# nintendac_mini.net
KiCad netlist of a schematic drawn in EAGLE
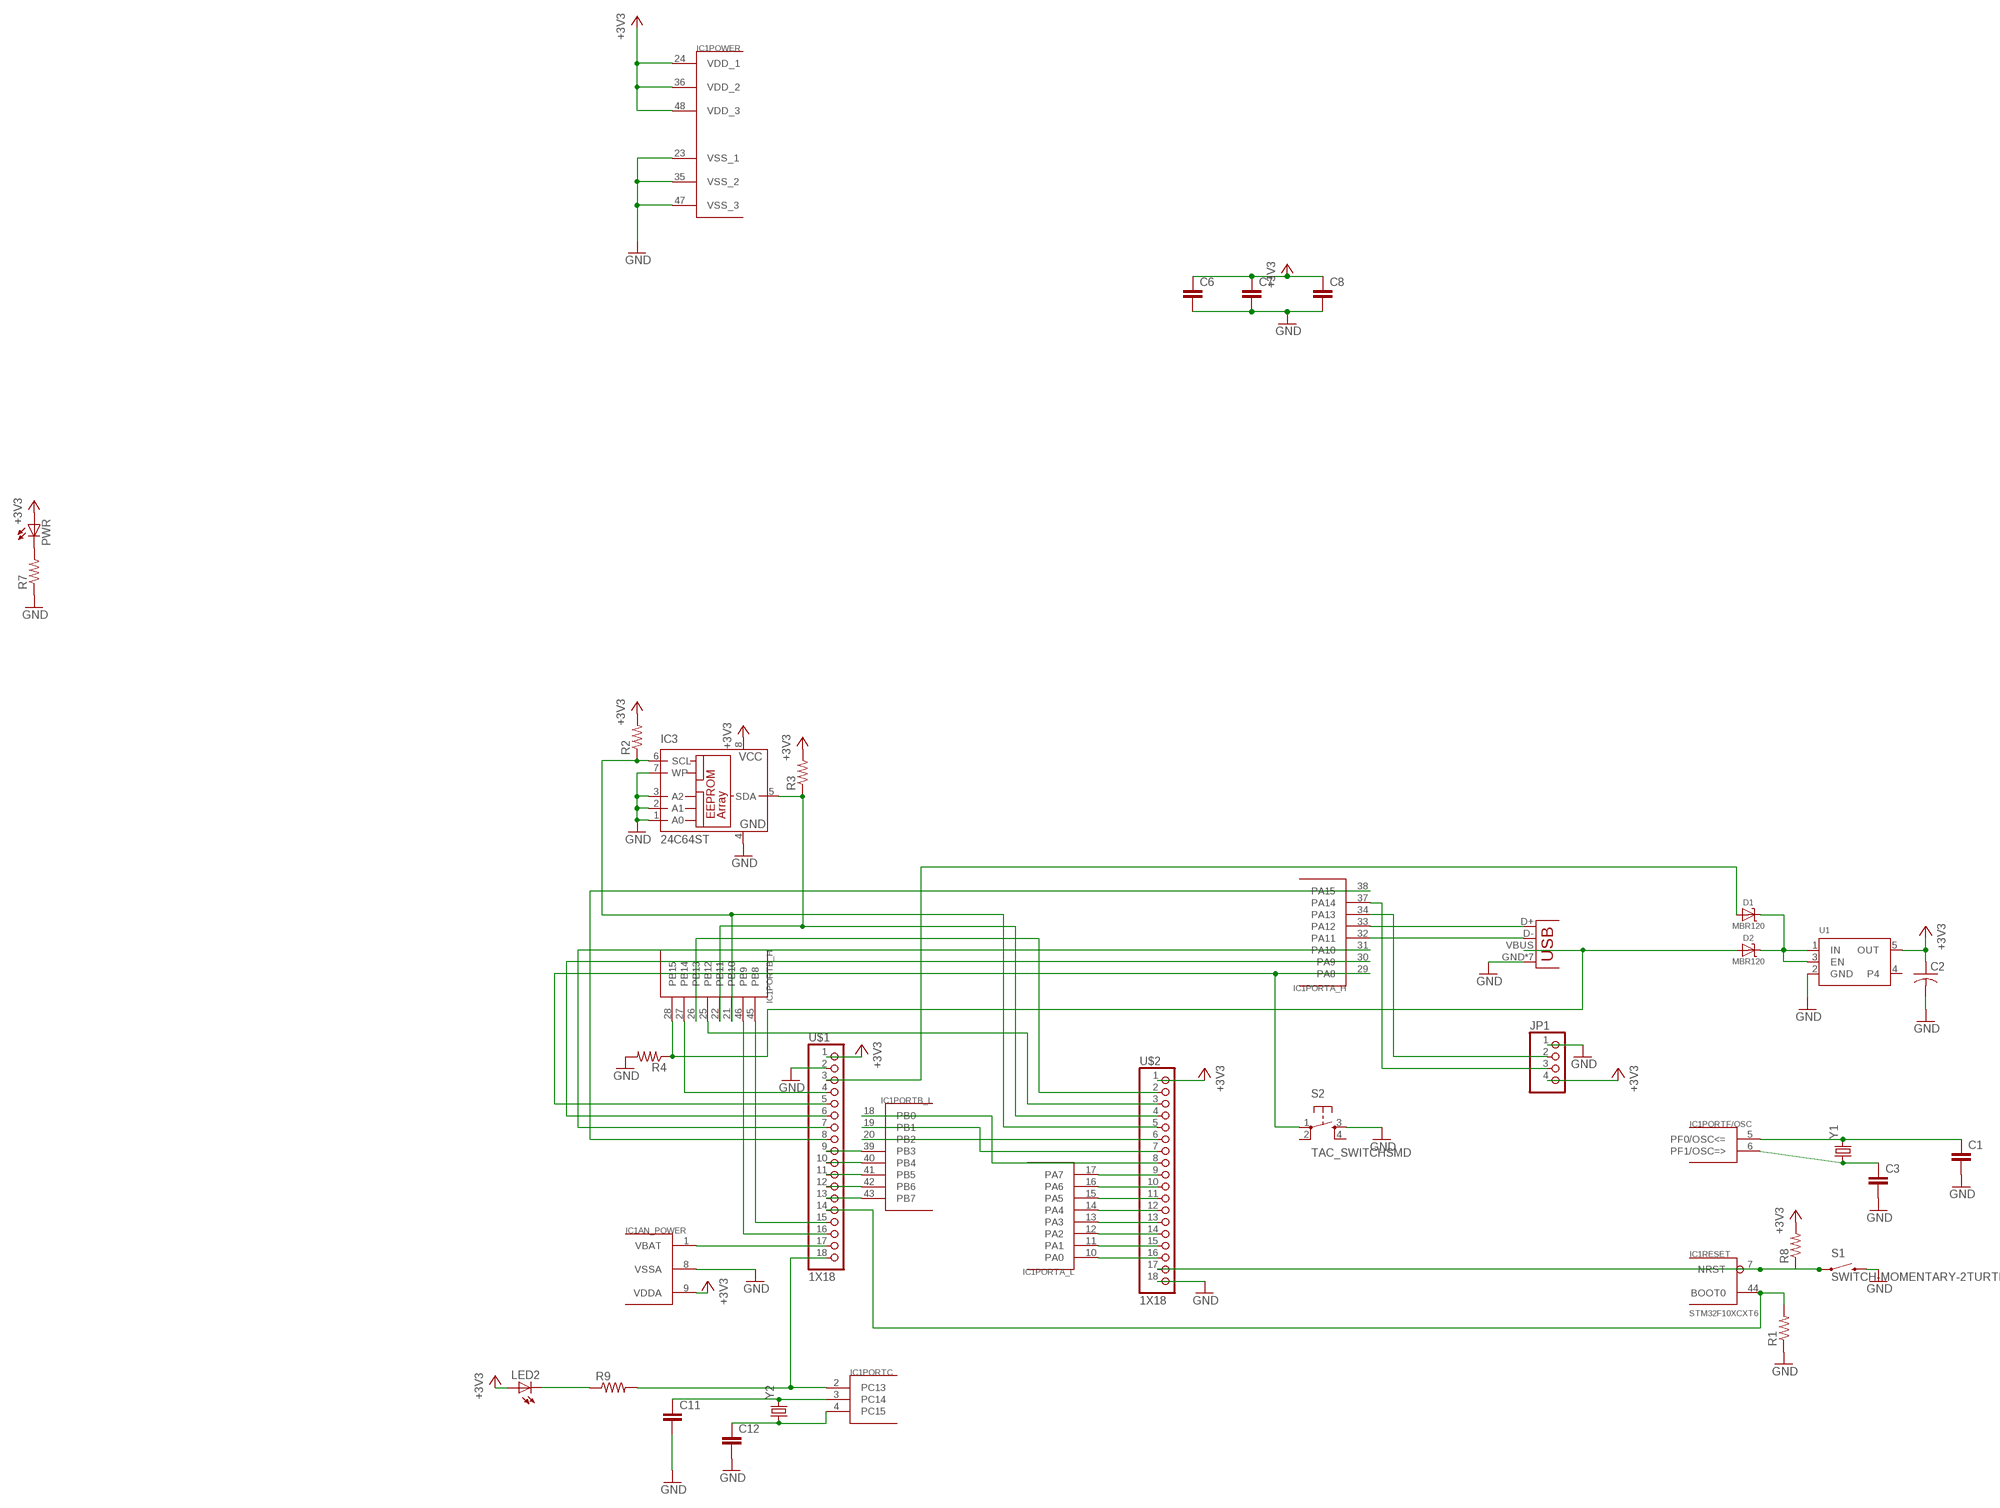
[diagram p0: schematic, sheet 1]

(export (version "E")
  (design (tool "Eeschema 10.0.6"))
  (components
    (comp (ref "C1")
      (value "CAP0805")
      (footprint "eagle-import:0805")
      (libsource (lib "eagle-import") (part "CAP0805"))
    )
    (comp (ref "C2")
      (value "C-USC1210")
      (footprint "eagle-import:C1210")
      (libsource (lib "eagle-import") (part "C-USC1210"))
    )
    (comp (ref "C3")
      (value "CAP0805")
      (footprint "eagle-import:0805")
      (libsource (lib "eagle-import") (part "CAP0805"))
    )
    (comp (ref "C6")
      (value "CAP0805")
      (footprint "eagle-import:0805")
      (libsource (lib "eagle-import") (part "CAP0805"))
    )
    (comp (ref "C7")
      (value "CAP0805")
      (footprint "eagle-import:0805")
      (libsource (lib "eagle-import") (part "CAP0805"))
    )
    (comp (ref "C8")
      (value "CAP0805")
      (footprint "eagle-import:0805")
      (libsource (lib "eagle-import") (part "CAP0805"))
    )
    (comp (ref "C11")
      (value "CAP0805")
      (footprint "eagle-import:0805")
      (libsource (lib "eagle-import") (part "CAP0805"))
    )
    (comp (ref "C12")
      (value "CAP0805")
      (footprint "eagle-import:0805")
      (libsource (lib "eagle-import") (part "CAP0805"))
    )
    (comp (ref "D1")
      (value "MBR120")
      (footprint "eagle-import:SOD-123")
      (libsource (lib "eagle-import") (part "DIODE-SCHOTTKYSOD-123"))
    )
    (comp (ref "D2")
      (value "MBR120")
      (footprint "eagle-import:SOD-123")
      (libsource (lib "eagle-import") (part "DIODE-SCHOTTKYSOD-123"))
    )
    (comp (ref "IC1")
      (value "STM32F10XCXT6")
      (footprint "eagle-import:TQFP48")
      (libsource (lib "eagle-import") (part "STM32F10XCXT6"))
    )
    (comp (ref "IC3")
      (value "24C64ST")
      (footprint "eagle-import:TSSOP8")
      (fields (field (name "MPN") "CAT24C64YI-GT3"))
      (libsource (lib "eagle-import") (part "24STC64"))
    )
    (comp (ref "JP1")
      (value "PINHD-1X4")
      (footprint "eagle-import:1X04")
      (libsource (lib "eagle-import") (part "PINHD-1X4"))
    )
    (comp (ref "LED2")
      (value "LEDCHIP-LED0805")
      (footprint "eagle-import:CHIP-LED0805")
      (libsource (lib "eagle-import") (part "LEDCHIP-LED0805"))
    )
    (comp (ref "PWR")
      (value "LEDCHIP-LED0805")
      (footprint "eagle-import:CHIP-LED0805")
      (libsource (lib "eagle-import") (part "LEDCHIP-LED0805"))
    )
    (comp (ref "R1")
      (value "RESISTOR0805-RES")
      (footprint "eagle-import:0805")
      (libsource (lib "eagle-import") (part "RESISTOR0805-RES"))
    )
    (comp (ref "R2")
      (value "RESISTOR0805-RES")
      (footprint "eagle-import:0805")
      (libsource (lib "eagle-import") (part "RESISTOR0805-RES"))
    )
    (comp (ref "R3")
      (value "RESISTOR0805-RES")
      (footprint "eagle-import:0805")
      (libsource (lib "eagle-import") (part "RESISTOR0805-RES"))
    )
    (comp (ref "R4")
      (value "RESISTOR0805-RES")
      (footprint "eagle-import:0805")
      (libsource (lib "eagle-import") (part "RESISTOR0805-RES"))
    )
    (comp (ref "R7")
      (value "RESISTOR0805-RES")
      (footprint "eagle-import:0805")
      (libsource (lib "eagle-import") (part "RESISTOR0805-RES"))
    )
    (comp (ref "R8")
      (value "RESISTOR0805-RES")
      (footprint "eagle-import:0805")
      (libsource (lib "eagle-import") (part "RESISTOR0805-RES"))
    )
    (comp (ref "R9")
      (value "RESISTOR0805-RES")
      (footprint "eagle-import:0805")
      (libsource (lib "eagle-import") (part "RESISTOR0805-RES"))
    )
    (comp (ref "S1")
      (value "SWITCH-MOMENTARY-2TURTLE")
      (footprint "eagle-import:KMR2")
      (libsource (lib "eagle-import") (part "SWITCH-MOMENTARY-2TURTLE"))
    )
    (comp (ref "S2")
      (value "TAC_SWITCHSMD")
      (footprint "eagle-import:TACTILE-SWITCH-SMD")
      (libsource (lib "eagle-import") (part "TAC_SWITCHSMD"))
    )
    (comp (ref "U$1")
      (value "1X18")
      (footprint "eagle-import:1X18")
      (libsource (lib "eagle-import") (part "1X18"))
    )
    (comp (ref "U$2")
      (value "1X18")
      (footprint "eagle-import:1X18")
      (libsource (lib "eagle-import") (part "1X18"))
    )
    (comp (ref "U1")
      (value "VREG_SOT23-5")
      (footprint "eagle-import:SOT23-5")
      (libsource (lib "eagle-import") (part "VREG_SOT23-5"))
    )
    (comp (ref "X1")
      (value "USB-MICROB")
      (footprint "eagle-import:USB-MICROB")
      (libsource (lib "eagle-import") (part "USB-MICROB"))
    )
    (comp (ref "Y1")
      (value "CRYSTALHC49US")
      (footprint "eagle-import:HC49US")
      (libsource (lib "eagle-import") (part "CRYSTALHC49US"))
    )
    (comp (ref "Y2")
      (value "CRYSTALTC26H_EZ")
      (footprint "eagle-import:TC26HEZ")
      (libsource (lib "eagle-import") (part "CRYSTALTC26H_EZ"))
    )
  )
  (nets
    (net (code "1") (name "+3V3") (class "Default")
      (node (ref "C2") (pin "1") (pinfunction "1_1") (pintype "passive"))
      (node (ref "C6") (pin "1") (pinfunction "1_1") (pintype "passive"))
      (node (ref "C7") (pin "1") (pinfunction "1_1") (pintype "passive"))
      (node (ref "C8") (pin "1") (pinfunction "1_1") (pintype "passive"))
      (node (ref "IC1") (pin "24") (pinfunction "VDD_1_24") (pintype "power_in"))
      (node (ref "IC1") (pin "36") (pinfunction "VDD_2_36") (pintype "power_in"))
      (node (ref "IC1") (pin "48") (pinfunction "VDD_3_48") (pintype "power_in"))
      (node (ref "IC1") (pin "9") (pinfunction "VDDA_9") (pintype "power_in"))
      (node (ref "IC3") (pin "8") (pinfunction "VCC_8") (pintype "power_in"))
      (node (ref "JP1") (pin "4") (pinfunction "4_4") (pintype "passive"))
      (node (ref "LED2") (pin "A") (pinfunction "A_A") (pintype "passive"))
      (node (ref "PWR") (pin "A") (pinfunction "A_A") (pintype "passive"))
      (node (ref "R2") (pin "2") (pinfunction "2_2") (pintype "passive"))
      (node (ref "R3") (pin "2") (pinfunction "2_2") (pintype "passive"))
      (node (ref "R8") (pin "2") (pinfunction "2_2") (pintype "passive"))
      (node (ref "U$1") (pin "1") (pinfunction "1_1") (pintype "passive"))
      (node (ref "U$2") (pin "1") (pinfunction "1_1") (pintype "passive"))
      (node (ref "U1") (pin "5") (pinfunction "OUT_5") (pintype "power_in"))
    )
    (net (code "2") (name "GND") (class "Default")
      (node (ref "C1") (pin "2") (pinfunction "2_2") (pintype "passive"))
      (node (ref "C11") (pin "2") (pinfunction "2_2") (pintype "passive"))
      (node (ref "C12") (pin "2") (pinfunction "2_2") (pintype "passive"))
      (node (ref "C2") (pin "2") (pinfunction "2_2") (pintype "passive"))
      (node (ref "C3") (pin "2") (pinfunction "2_2") (pintype "passive"))
      (node (ref "C6") (pin "2") (pinfunction "2_2") (pintype "passive"))
      (node (ref "C7") (pin "2") (pinfunction "2_2") (pintype "passive"))
      (node (ref "C8") (pin "2") (pinfunction "2_2") (pintype "passive"))
      (node (ref "IC1") (pin "23") (pinfunction "VSS_1_23") (pintype "power_in"))
      (node (ref "IC1") (pin "35") (pinfunction "VSS_2_35") (pintype "power_in"))
      (node (ref "IC1") (pin "47") (pinfunction "VSS_3_47") (pintype "power_in"))
      (node (ref "IC1") (pin "8") (pinfunction "VSSA_8") (pintype "power_in"))
      (node (ref "IC3") (pin "1") (pinfunction "A0_1") (pintype "input"))
      (node (ref "IC3") (pin "2") (pinfunction "A1_2") (pintype "input"))
      (node (ref "IC3") (pin "3") (pinfunction "A2_3") (pintype "input"))
      (node (ref "IC3") (pin "4") (pinfunction "GND_4") (pintype "power_in"))
      (node (ref "IC3") (pin "7") (pinfunction "WP_7") (pintype "input"))
      (node (ref "JP1") (pin "1") (pinfunction "1_1") (pintype "passive"))
      (node (ref "R1") (pin "1") (pinfunction "1_1") (pintype "passive"))
      (node (ref "R4") (pin "2") (pinfunction "2_2") (pintype "passive"))
      (node (ref "R7") (pin "1") (pinfunction "1_1") (pintype "passive"))
      (node (ref "S1") (pin "3") (pinfunction "2_3") (pintype "passive"))
      (node (ref "S2") (pin "3") (pinfunction "3_3") (pintype "passive"))
      (node (ref "U$1") (pin "2") (pinfunction "2_2") (pintype "passive"))
      (node (ref "U$2") (pin "18") (pinfunction "18_18") (pintype "passive"))
      (node (ref "U1") (pin "2") (pinfunction "GND_2") (pintype "power_in"))
      (node (ref "X1") (pin "GND") (pinfunction "GND_GND") (pintype "bidirectional"))
      (node (ref "X1") (pin "P1") (pinfunction "GND_P1") (pintype "bidirectional"))
      (node (ref "X1") (pin "P2") (pinfunction "GND_P2") (pintype "bidirectional"))
      (node (ref "X1") (pin "P3") (pinfunction "GND_P3") (pintype "bidirectional"))
      (node (ref "X1") (pin "P4") (pinfunction "GND_P4") (pintype "bidirectional"))
      (node (ref "X1") (pin "P5") (pinfunction "GND_P5") (pintype "bidirectional"))
      (node (ref "X1") (pin "P6") (pinfunction "GND_P6") (pintype "bidirectional"))
    )
    (net (code "3") (name "Net-(D1-PadA)") (class "Default")
      (node (ref "D1") (pin "A") (pinfunction "A_A") (pintype "passive"))
      (node (ref "U$1") (pin "3") (pinfunction "3_3") (pintype "passive"))
    )
    (net (code "4") (name "Net-(IC1A-VBAT)") (class "Default")
      (node (ref "IC1") (pin "1") (pinfunction "VBAT_1") (pintype "power_in"))
      (node (ref "U$1") (pin "17") (pinfunction "17_17") (pintype "passive"))
    )
    (net (code "5") (name "Net-(IC1B-PA8)") (class "Default")
      (node (ref "IC1") (pin "29") (pinfunction "PA8_29") (pintype "bidirectional"))
      (node (ref "S2") (pin "1") (pinfunction "1_1") (pintype "passive"))
      (node (ref "U$1") (pin "5") (pinfunction "5_5") (pintype "passive"))
    )
    (net (code "6") (name "Net-(IC1B-PA9)") (class "Default")
      (node (ref "IC1") (pin "30") (pinfunction "PA9_30") (pintype "bidirectional"))
      (node (ref "U$1") (pin "6") (pinfunction "6_6") (pintype "passive"))
    )
    (net (code "7") (name "Net-(IC1B-PA10)") (class "Default")
      (node (ref "IC1") (pin "31") (pinfunction "PA10_31") (pintype "bidirectional"))
      (node (ref "U$1") (pin "7") (pinfunction "7_7") (pintype "passive"))
    )
    (net (code "8") (name "Net-(IC1B-PA11)") (class "Default")
      (node (ref "IC1") (pin "32") (pinfunction "PA11_32") (pintype "bidirectional"))
      (node (ref "X1") (pin "D-") (pinfunction "D-_D-") (pintype "bidirectional"))
    )
    (net (code "9") (name "Net-(IC1B-PA12)") (class "Default")
      (node (ref "IC1") (pin "33") (pinfunction "PA12_33") (pintype "bidirectional"))
      (node (ref "X1") (pin "D+") (pinfunction "D+_D+") (pintype "bidirectional"))
    )
    (net (code "10") (name "Net-(IC1B-PA13)") (class "Default")
      (node (ref "IC1") (pin "34") (pinfunction "PA13_34") (pintype "bidirectional"))
      (node (ref "JP1") (pin "2") (pinfunction "2_2") (pintype "passive"))
    )
    (net (code "11") (name "Net-(IC1B-PA14)") (class "Default")
      (node (ref "IC1") (pin "37") (pinfunction "PA14_37") (pintype "bidirectional"))
      (node (ref "JP1") (pin "3") (pinfunction "3_3") (pintype "passive"))
    )
    (net (code "12") (name "Net-(IC1B-PA15)") (class "Default")
      (node (ref "IC1") (pin "38") (pinfunction "PA15_38") (pintype "bidirectional"))
      (node (ref "U$1") (pin "8") (pinfunction "8_8") (pintype "passive"))
    )
    (net (code "13") (name "Net-(IC1C-PA0)") (class "Default")
      (node (ref "IC1") (pin "10") (pinfunction "PA0_10") (pintype "bidirectional"))
      (node (ref "U$2") (pin "16") (pinfunction "16_16") (pintype "passive"))
    )
    (net (code "14") (name "Net-(IC1C-PA1)") (class "Default")
      (node (ref "IC1") (pin "11") (pinfunction "PA1_11") (pintype "bidirectional"))
      (node (ref "U$2") (pin "15") (pinfunction "15_15") (pintype "passive"))
    )
    (net (code "15") (name "Net-(IC1C-PA2)") (class "Default")
      (node (ref "IC1") (pin "12") (pinfunction "PA2_12") (pintype "bidirectional"))
      (node (ref "U$2") (pin "14") (pinfunction "14_14") (pintype "passive"))
    )
    (net (code "16") (name "Net-(IC1C-PA3)") (class "Default")
      (node (ref "IC1") (pin "13") (pinfunction "PA3_13") (pintype "bidirectional"))
      (node (ref "U$2") (pin "13") (pinfunction "13_13") (pintype "passive"))
    )
    (net (code "17") (name "Net-(IC1C-PA4)") (class "Default")
      (node (ref "IC1") (pin "14") (pinfunction "PA4_14") (pintype "bidirectional"))
      (node (ref "U$2") (pin "12") (pinfunction "12_12") (pintype "passive"))
    )
    (net (code "18") (name "Net-(IC1C-PA5)") (class "Default")
      (node (ref "IC1") (pin "15") (pinfunction "PA5_15") (pintype "bidirectional"))
      (node (ref "U$2") (pin "11") (pinfunction "11_11") (pintype "passive"))
    )
    (net (code "19") (name "Net-(IC1C-PA6)") (class "Default")
      (node (ref "IC1") (pin "16") (pinfunction "PA6_16") (pintype "bidirectional"))
      (node (ref "U$2") (pin "10") (pinfunction "10_10") (pintype "passive"))
    )
    (net (code "20") (name "Net-(IC1C-PA7)") (class "Default")
      (node (ref "IC1") (pin "17") (pinfunction "PA7_17") (pintype "bidirectional"))
      (node (ref "U$2") (pin "9") (pinfunction "9_9") (pintype "passive"))
    )
    (net (code "21") (name "Net-(IC1D-PB8)") (class "Default")
      (node (ref "IC1") (pin "45") (pinfunction "PB8_45") (pintype "bidirectional"))
      (node (ref "U$1") (pin "15") (pinfunction "15_15") (pintype "passive"))
    )
    (net (code "22") (name "Net-(IC1D-PB9)") (class "Default")
      (node (ref "IC1") (pin "46") (pinfunction "PB9_46") (pintype "bidirectional"))
      (node (ref "U$1") (pin "16") (pinfunction "16_16") (pintype "passive"))
    )
    (net (code "23") (name "Net-(IC1D-PB10)") (class "Default")
      (node (ref "IC1") (pin "21") (pinfunction "PB10_21") (pintype "bidirectional"))
      (node (ref "IC3") (pin "6") (pinfunction "SCL_6") (pintype "input"))
      (node (ref "R2") (pin "1") (pinfunction "1_1") (pintype "passive"))
      (node (ref "U$2") (pin "5") (pinfunction "5_5") (pintype "passive"))
    )
    (net (code "24") (name "Net-(IC1D-PB11)") (class "Default")
      (node (ref "IC1") (pin "22") (pinfunction "PB11_22") (pintype "bidirectional"))
      (node (ref "IC3") (pin "5") (pinfunction "SDA_5") (pintype "bidirectional"))
      (node (ref "R3") (pin "1") (pinfunction "1_1") (pintype "passive"))
      (node (ref "U$2") (pin "4") (pinfunction "4_4") (pintype "passive"))
    )
    (net (code "25") (name "Net-(IC1D-PB12)") (class "Default")
      (node (ref "IC1") (pin "25") (pinfunction "PB12_25") (pintype "bidirectional"))
      (node (ref "U$2") (pin "3") (pinfunction "3_3") (pintype "passive"))
    )
    (net (code "26") (name "Net-(IC1D-PB13)") (class "Default")
      (node (ref "IC1") (pin "26") (pinfunction "PB13_26") (pintype "bidirectional"))
      (node (ref "U$2") (pin "2") (pinfunction "2_2") (pintype "passive"))
    )
    (net (code "27") (name "Net-(IC1D-PB14)") (class "Default")
      (node (ref "IC1") (pin "27") (pinfunction "PB14_27") (pintype "bidirectional"))
      (node (ref "U$1") (pin "4") (pinfunction "4_4") (pintype "passive"))
    )
    (net (code "28") (name "Net-(IC1D-PB15)") (class "Default")
      (node (ref "D2") (pin "A") (pinfunction "A_A") (pintype "passive"))
      (node (ref "IC1") (pin "28") (pinfunction "PB15_28") (pintype "bidirectional"))
      (node (ref "R4") (pin "1") (pinfunction "1_1") (pintype "passive"))
      (node (ref "X1") (pin "VBUS") (pinfunction "VBUS_VBUS") (pintype "bidirectional"))
    )
    (net (code "29") (name "Net-(IC1E-PB0)") (class "Default")
      (node (ref "IC1") (pin "18") (pinfunction "PB0_18") (pintype "bidirectional"))
      (node (ref "U$2") (pin "8") (pinfunction "8_8") (pintype "passive"))
    )
    (net (code "30") (name "Net-(IC1E-PB1)") (class "Default")
      (node (ref "IC1") (pin "19") (pinfunction "PB1_19") (pintype "bidirectional"))
      (node (ref "U$2") (pin "7") (pinfunction "7_7") (pintype "passive"))
    )
    (net (code "31") (name "Net-(IC1E-PB2)") (class "Default")
      (node (ref "IC1") (pin "20") (pinfunction "PB2_20") (pintype "bidirectional"))
      (node (ref "U$2") (pin "6") (pinfunction "6_6") (pintype "passive"))
    )
    (net (code "32") (name "Net-(IC1E-PB3)") (class "Default")
      (node (ref "IC1") (pin "39") (pinfunction "PB3_39") (pintype "bidirectional"))
      (node (ref "U$1") (pin "9") (pinfunction "9_9") (pintype "passive"))
    )
    (net (code "33") (name "Net-(IC1E-PB4)") (class "Default")
      (node (ref "IC1") (pin "40") (pinfunction "PB4_40") (pintype "bidirectional"))
      (node (ref "U$1") (pin "10") (pinfunction "10_10") (pintype "passive"))
    )
    (net (code "34") (name "Net-(IC1E-PB5)") (class "Default")
      (node (ref "IC1") (pin "41") (pinfunction "PB5_41") (pintype "bidirectional"))
      (node (ref "U$1") (pin "11") (pinfunction "11_11") (pintype "passive"))
    )
    (net (code "35") (name "Net-(IC1E-PB6)") (class "Default")
      (node (ref "IC1") (pin "42") (pinfunction "PB6_42") (pintype "bidirectional"))
      (node (ref "U$1") (pin "12") (pinfunction "12_12") (pintype "passive"))
    )
    (net (code "36") (name "Net-(IC1E-PB7)") (class "Default")
      (node (ref "IC1") (pin "43") (pinfunction "PB7_43") (pintype "bidirectional"))
      (node (ref "U$1") (pin "13") (pinfunction "13_13") (pintype "passive"))
    )
    (net (code "37") (name "Net-(IC1F-PC13)") (class "Default")
      (node (ref "IC1") (pin "2") (pinfunction "PC13_2") (pintype "bidirectional"))
      (node (ref "R9") (pin "2") (pinfunction "2_2") (pintype "passive"))
      (node (ref "U$1") (pin "18") (pinfunction "18_18") (pintype "passive"))
    )
    (net (code "38") (name "Net-(IC1F-PC14)") (class "Default")
      (node (ref "C11") (pin "1") (pinfunction "1_1") (pintype "passive"))
      (node (ref "IC1") (pin "3") (pinfunction "PC14_3") (pintype "bidirectional"))
      (node (ref "Y2") (pin "2") (pinfunction "2_2") (pintype "passive"))
    )
    (net (code "39") (name "Net-(IC1F-PC15)") (class "Default")
      (node (ref "C12") (pin "1") (pinfunction "1_1") (pintype "passive"))
      (node (ref "IC1") (pin "4") (pinfunction "PC15_4") (pintype "bidirectional"))
      (node (ref "Y2") (pin "1") (pinfunction "1_1") (pintype "passive"))
    )
    (net (code "40") (name "Net-(IC1G-PF0{slash}OSC<=)") (class "Default")
      (node (ref "C1") (pin "1") (pinfunction "1_1") (pintype "passive"))
      (node (ref "IC1") (pin "5") (pinfunction "PF0/OSC<=_5") (pintype "bidirectional"))
      (node (ref "Y1") (pin "2") (pinfunction "2_2") (pintype "passive"))
    )
    (net (code "41") (name "Net-(IC1G-PF1{slash}OSC=>)") (class "Default")
      (node (ref "C3") (pin "1") (pinfunction "1_1") (pintype "passive"))
      (node (ref "IC1") (pin "6") (pinfunction "PF1/OSC=>_6") (pintype "bidirectional"))
      (node (ref "Y1") (pin "1") (pinfunction "1_1") (pintype "passive"))
    )
    (net (code "42") (name "Net-(IC1I-BOOT0)") (class "Default")
      (node (ref "IC1") (pin "44") (pinfunction "BOOT0_44") (pintype "input"))
      (node (ref "R1") (pin "2") (pinfunction "2_2") (pintype "passive"))
      (node (ref "U$1") (pin "14") (pinfunction "14_14") (pintype "passive"))
    )
    (net (code "43") (name "Net-(IC1I-NRST)") (class "Default")
      (node (ref "IC1") (pin "7") (pinfunction "NRST_7") (pintype "input"))
      (node (ref "R8") (pin "1") (pinfunction "1_1") (pintype "passive"))
      (node (ref "S1") (pin "1") (pinfunction "1_1") (pintype "passive"))
      (node (ref "U$2") (pin "17") (pinfunction "17_17") (pintype "passive"))
    )
    (net (code "44") (name "Net-(LED2-PadC)") (class "Default")
      (node (ref "LED2") (pin "C") (pinfunction "C_C") (pintype "passive"))
      (node (ref "R9") (pin "1") (pinfunction "1_1") (pintype "passive"))
    )
    (net (code "45") (name "Net-(PWR-PadC)") (class "Default")
      (node (ref "PWR") (pin "C") (pinfunction "C_C") (pintype "passive"))
      (node (ref "R7") (pin "2") (pinfunction "2_2") (pintype "passive"))
    )
    (net (code "46") (name "Net-(U1-EN)") (class "Default")
      (node (ref "D1") (pin "C") (pinfunction "C_C") (pintype "passive"))
      (node (ref "D2") (pin "C") (pinfunction "C_C") (pintype "passive"))
      (node (ref "U1") (pin "1") (pinfunction "IN_1") (pintype "power_in"))
      (node (ref "U1") (pin "3") (pinfunction "EN_3") (pintype "input"))
    )
    (net (code "47") (name "unconnected-(S2-Pad2)") (class "Default")
      (node (ref "S2") (pin "2") (pinfunction "2_2") (pintype "passive"))
    )
    (net (code "48") (name "unconnected-(S2-Pad4)") (class "Default")
      (node (ref "S2") (pin "4") (pinfunction "4_4") (pintype "passive"))
    )
    (net (code "49") (name "unconnected-(U1-P4-Pad4)") (class "Default")
      (node (ref "U1") (pin "4") (pinfunction "P4_4") (pintype "bidirectional"))
    )
  )
)
